# DIV2_8B.net
KiCad netlist of a schematic drawn in Altium Designer
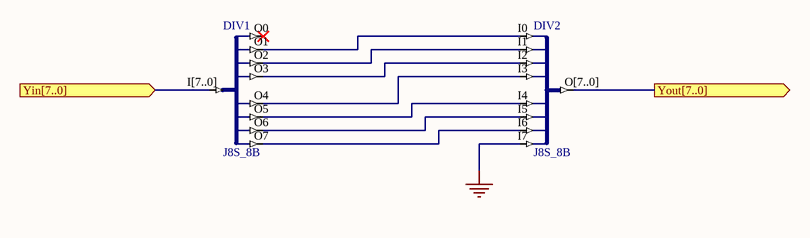
[diagram p0: DIV2_8B.SCHDOC]

(export (version "E")
  (design (tool "Eeschema 10.0.6"))
  (components
    (comp (ref "DIV1")
      (value "J8S_8B")
      (description "8-Bit input bus to 8 single pin outputs")
      (fields (field (name "PUBLISHER") "Altium Limited"))
      (libsource (lib "FPGA Generic") (part "J8B_8S"))
    )
    (comp (ref "DIV2")
      (value "J8S_8B")
      (description "8 Single pin inputs to single 8-Bit output bus")
      (fields (field (name "PUBLISHER") "Altium Limited"))
      (libsource (lib "FPGA Generic") (part "J8S_8B"))
    )
  )
  (nets
    (net (code "17") (name "/Yin[7..0]") (class "Default")
      (node (ref "DIV1") (pin "I[7..0]") (pinfunction "I[7..0]_I[7..0]") (pintype "input"))
    )
    (net (code "18") (name "/Yout[7..0]") (class "Default")
      (node (ref "DIV2") (pin "O[7..0]") (pinfunction "O[7..0]_O[7..0]") (pintype "output"))
    )
    (net (code "19") (name "GND") (class "Default")
      (node (ref "DIV2") (pin "I7") (pinfunction "I7_I7") (pintype "input"))
    )
    (net (code "20") (name "Net-(DIV1-PadO1)") (class "Default")
      (node (ref "DIV1") (pin "O1") (pinfunction "O1_O1") (pintype "output"))
      (node (ref "DIV2") (pin "I0") (pinfunction "I0_I0") (pintype "input"))
    )
    (net (code "21") (name "Net-(DIV1-PadO2)") (class "Default")
      (node (ref "DIV1") (pin "O2") (pinfunction "O2_O2") (pintype "output"))
      (node (ref "DIV2") (pin "I1") (pinfunction "I1_I1") (pintype "input"))
    )
    (net (code "22") (name "Net-(DIV1-PadO3)") (class "Default")
      (node (ref "DIV1") (pin "O3") (pinfunction "O3_O3") (pintype "output"))
      (node (ref "DIV2") (pin "I2") (pinfunction "I2_I2") (pintype "input"))
    )
    (net (code "23") (name "Net-(DIV1-PadO4)") (class "Default")
      (node (ref "DIV1") (pin "O4") (pinfunction "O4_O4") (pintype "output"))
      (node (ref "DIV2") (pin "I3") (pinfunction "I3_I3") (pintype "input"))
    )
    (net (code "24") (name "Net-(DIV1-PadO5)") (class "Default")
      (node (ref "DIV1") (pin "O5") (pinfunction "O5_O5") (pintype "output"))
      (node (ref "DIV2") (pin "I4") (pinfunction "I4_I4") (pintype "input"))
    )
    (net (code "25") (name "Net-(DIV1-PadO6)") (class "Default")
      (node (ref "DIV1") (pin "O6") (pinfunction "O6_O6") (pintype "output"))
      (node (ref "DIV2") (pin "I5") (pinfunction "I5_I5") (pintype "input"))
    )
    (net (code "26") (name "Net-(DIV1-PadO7)") (class "Default")
      (node (ref "DIV1") (pin "O7") (pinfunction "O7_O7") (pintype "output"))
      (node (ref "DIV2") (pin "I6") (pinfunction "I6_I6") (pintype "input"))
    )
    (net (code "27") (name "unconnected-(DIV1-PadO0)") (class "Default")
      (node (ref "DIV1") (pin "O0") (pinfunction "O0_O0") (pintype "output+no_connect"))
    )
  )
)
